# FT245.net
KiCad netlist of a schematic drawn in Altium Designer
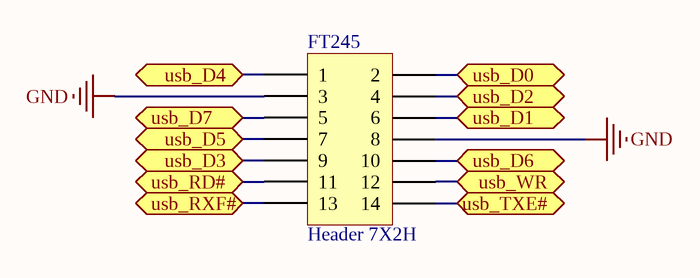
[diagram p0: FT245.SchDoc]

(export (version "E")
  (design (tool "Eeschema 10.0.6"))
  (components
    (comp (ref "FT245")
      (value "Header 7X2H")
      (footprint "HDR2X7")
      (description "Header, 7-Pin, Dual row, Right Angle")
      (fields (field (name "PUBLISHER") "Altium Limited"))
      (libsource (lib "Miscellaneous Connectors") (part "Header 7X2H"))
    )
  )
  (nets
    (net (code "1") (name "/usb_D0") (class "Default")
      (node (ref "FT245") (pin "2") (pinfunction "2_2") (pintype "passive"))
    )
    (net (code "2") (name "/usb_D1") (class "Default")
      (node (ref "FT245") (pin "6") (pinfunction "6_6") (pintype "passive"))
    )
    (net (code "3") (name "/usb_D2") (class "Default")
      (node (ref "FT245") (pin "4") (pinfunction "4_4") (pintype "passive"))
    )
    (net (code "4") (name "/usb_D3") (class "Default")
      (node (ref "FT245") (pin "9") (pinfunction "9_9") (pintype "passive"))
    )
    (net (code "5") (name "/usb_D4") (class "Default")
      (node (ref "FT245") (pin "1") (pinfunction "1_1") (pintype "passive"))
    )
    (net (code "6") (name "/usb_D5") (class "Default")
      (node (ref "FT245") (pin "7") (pinfunction "7_7") (pintype "passive"))
    )
    (net (code "7") (name "/usb_D6") (class "Default")
      (node (ref "FT245") (pin "10") (pinfunction "10_10") (pintype "passive"))
    )
    (net (code "8") (name "/usb_D7") (class "Default")
      (node (ref "FT245") (pin "5") (pinfunction "5_5") (pintype "passive"))
    )
    (net (code "9") (name "/usb_RD#") (class "Default")
      (node (ref "FT245") (pin "11") (pinfunction "11_11") (pintype "passive"))
    )
    (net (code "10") (name "/usb_RXF#") (class "Default")
      (node (ref "FT245") (pin "13") (pinfunction "13_13") (pintype "passive"))
    )
    (net (code "11") (name "/usb_TXE#") (class "Default")
      (node (ref "FT245") (pin "14") (pinfunction "14_14") (pintype "passive"))
    )
    (net (code "12") (name "/usb_WR") (class "Default")
      (node (ref "FT245") (pin "12") (pinfunction "12_12") (pintype "passive"))
    )
    (net (code "13") (name "GND") (class "Default")
      (node (ref "FT245") (pin "3") (pinfunction "3_3") (pintype "passive"))
      (node (ref "FT245") (pin "8") (pinfunction "8_8") (pintype "passive"))
    )
  )
)
